# HDDA_encoder.net
KiCad netlist of a schematic drawn in Altium Designer
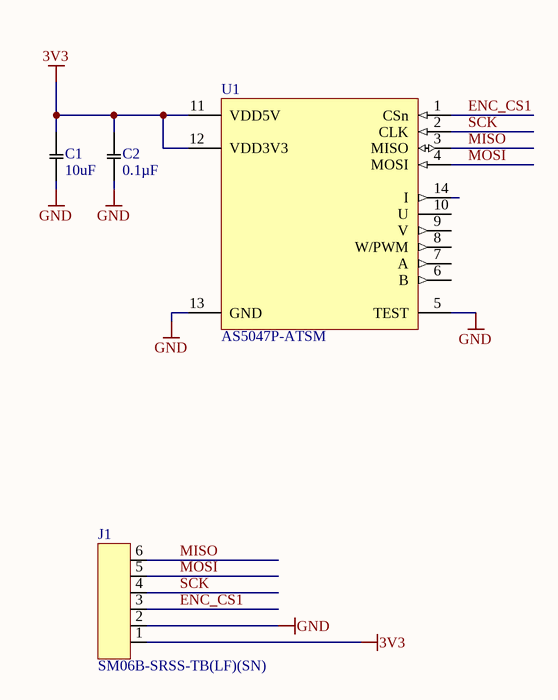
[diagram p0: HDDA_encoder.SchDoc]

(export (version "E")
  (design (tool "Eeschema 10.0.6"))
  (components
    (comp (ref "C1")
      (value "10uF")
      (footprint "C0603")
      (description "CAP CER 10UF 10V 10% X5R 0603")
      (fields
        (field (name "MANUFACTURER") "TDK Corporation")
        (field (name "MANUFACTURER PART NUMBER") "C1608X5R1A106K080AC")
      )
      (libsource (lib "capacitors") (part "C"))
    )
    (comp (ref "C2")
      (value "0.1µF")
      (footprint "C0402")
      (description "CAP CER 0.1UF 50V 10% X7R 0402")
      (fields
        (field (name "MANUFACTURER PART NUMBER") "C1005X7R1H104K050BB")
        (field (name "MANUFACTURER") "TDK Corporation")
      )
      (libsource (lib "capacitors") (part "C"))
    )
    (comp (ref "J1")
      (value "SM06B-SRSS-TB(LF)(SN)")
      (footprint "SM06B-SRSS-TB")
      (description "CONN HEADER SH 6POS SIDE 1MM TIN")
      (fields (field (name "MANUFACTURER") "JST Sales America Inc"))
      (libsource (lib "connectors_interconnects") (part "CONN_1_ROW_006_POS"))
    )
    (comp (ref "U1")
      (value "AS5047P-ATSM")
      (footprint "AS5047X")
      (description "IC ENCODER ROTARY 14TSSOP")
      (fields (field (name "MANUFACTURER") "ams"))
      (libsource (lib "sensors_transducers") (part "AS5047P"))
    )
  )
  (nets
    (net (code "1") (name "/ENC_CS1") (class "Default")
      (node (ref "J1") (pin "3") (pinfunction "3_3") (pintype "passive"))
      (node (ref "U1") (pin "1") (pinfunction "CSn_1") (pintype "input"))
    )
    (net (code "2") (name "/MISO") (class "Default")
      (node (ref "J1") (pin "6") (pinfunction "6_6") (pintype "passive"))
      (node (ref "U1") (pin "3") (pinfunction "MISO_3") (pintype "bidirectional"))
    )
    (net (code "3") (name "/MOSI") (class "Default")
      (node (ref "J1") (pin "5") (pinfunction "5_5") (pintype "passive"))
      (node (ref "U1") (pin "4") (pinfunction "MOSI_4") (pintype "input"))
    )
    (net (code "4") (name "/SCK") (class "Default")
      (node (ref "J1") (pin "4") (pinfunction "4_4") (pintype "passive"))
      (node (ref "U1") (pin "2") (pinfunction "CLK_2") (pintype "input"))
    )
    (net (code "5") (name "3V3") (class "Default")
      (node (ref "C1") (pin "1") (pinfunction "1_1") (pintype "passive"))
      (node (ref "C2") (pin "1") (pinfunction "1_1") (pintype "passive"))
      (node (ref "J1") (pin "1") (pinfunction "1_1") (pintype "passive"))
      (node (ref "U1") (pin "11") (pinfunction "VDD5V_11") (pintype "power_in"))
      (node (ref "U1") (pin "12") (pinfunction "VDD3V3_12") (pintype "power_in"))
    )
    (net (code "6") (name "GND") (class "Default")
      (node (ref "C1") (pin "2") (pinfunction "2_2") (pintype "passive"))
      (node (ref "C2") (pin "2") (pinfunction "2_2") (pintype "passive"))
      (node (ref "J1") (pin "2") (pinfunction "2_2") (pintype "passive"))
      (node (ref "U1") (pin "13") (pinfunction "GND_13") (pintype "power_in"))
      (node (ref "U1") (pin "5") (pinfunction "TEST_5") (pintype "passive"))
    )
    (net (code "7") (name "unconnected-(U1-A-Pad7)") (class "Default")
      (node (ref "U1") (pin "7") (pinfunction "A_7") (pintype "output"))
    )
    (net (code "8") (name "unconnected-(U1-B-Pad6)") (class "Default")
      (node (ref "U1") (pin "6") (pinfunction "B_6") (pintype "output"))
    )
    (net (code "9") (name "unconnected-(U1-I-Pad14)") (class "Default")
      (node (ref "U1") (pin "14") (pinfunction "I_14") (pintype "output"))
    )
    (net (code "10") (name "unconnected-(U1-U-Pad10)") (class "Default")
      (node (ref "U1") (pin "10") (pinfunction "U_10") (pintype "passive"))
    )
    (net (code "11") (name "unconnected-(U1-V-Pad9)") (class "Default")
      (node (ref "U1") (pin "9") (pinfunction "V_9") (pintype "output"))
    )
    (net (code "12") (name "unconnected-(U1-W{slash}PWM-Pad8)") (class "Default")
      (node (ref "U1") (pin "8") (pinfunction "W/PWM_8") (pintype "output"))
    )
  )
)
